# PCB_Arduino_V2_0_PC.net
KiCad netlist of a schematic drawn in EAGLE
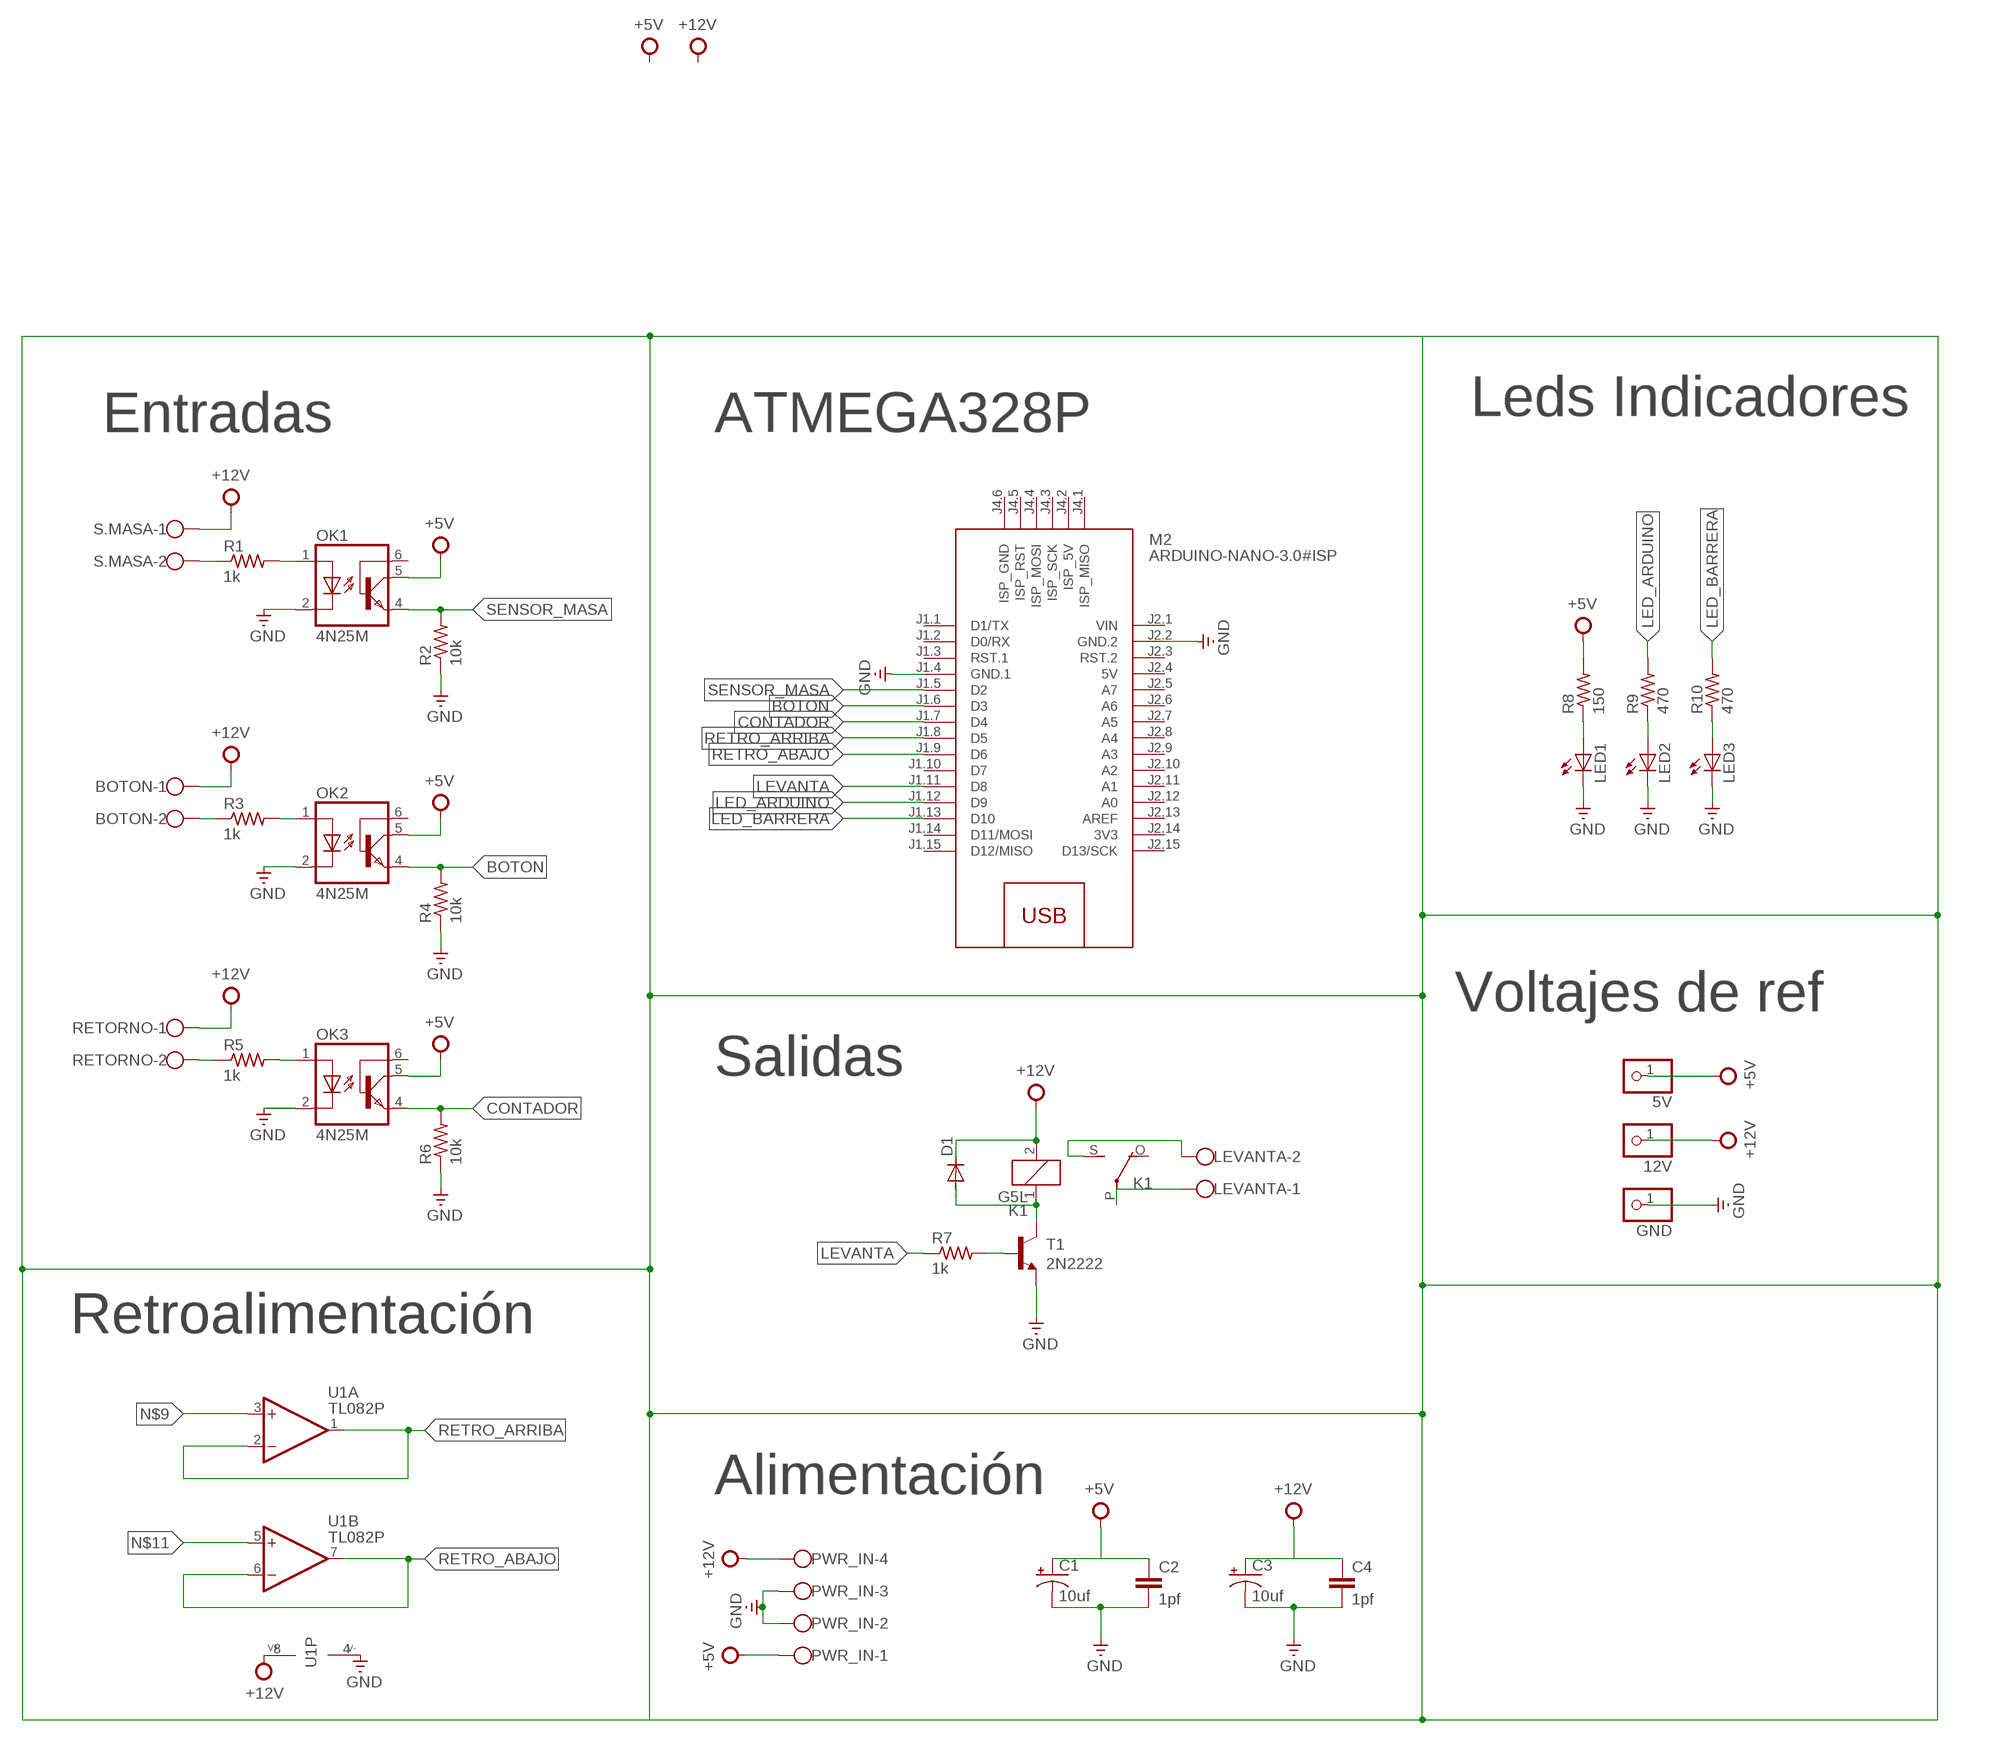
[diagram p0: schematic, sheet 1]

(export (version "E")
  (design (tool "Eeschema 10.0.6"))
  (components
    (comp (ref "5V")
      (value "PINHD-1X1")
      (footprint "eagle-import:1X01")
      (libsource (lib "eagle-import") (part "PINHD-1X1"))
    )
    (comp (ref "12V")
      (value "PINHD-1X1")
      (footprint "eagle-import:1X01")
      (libsource (lib "eagle-import") (part "PINHD-1X1"))
    )
    (comp (ref "BOTON")
      (value "W237-102")
      (footprint "eagle-import:W237-102")
      (fields (field (name "MPN") "237-102"))
      (libsource (lib "eagle-import") (part "W237-102"))
    )
    (comp (ref "C1")
      (value "10uf")
      (footprint "eagle-import:E2,5-6")
      (libsource (lib "eagle-import") (part "CPOL-USE2.5-6"))
    )
    (comp (ref "C2")
      (value "1pf")
      (footprint "eagle-import:C2.5-3")
      (libsource (lib "eagle-import") (part "C2,5-3"))
    )
    (comp (ref "C3")
      (value "10uf")
      (footprint "eagle-import:E2,5-6")
      (libsource (lib "eagle-import") (part "CPOL-USE2.5-6"))
    )
    (comp (ref "C4")
      (value "1pf")
      (footprint "eagle-import:C2.5-3")
      (libsource (lib "eagle-import") (part "C2,5-3"))
    )
    (comp (ref "D1")
      (value "1N4148DO35-7")
      (footprint "eagle-import:DO35-7")
      (libsource (lib "eagle-import") (part "1N4148DO35-7"))
    )
    (comp (ref "GND")
      (value "PINHD-1X1")
      (footprint "eagle-import:1X01")
      (libsource (lib "eagle-import") (part "PINHD-1X1"))
    )
    (comp (ref "K1")
      (value "G5L")
      (footprint "eagle-import:G5LE")
      (libsource (lib "eagle-import") (part "G5L"))
    )
    (comp (ref "LED1")
      (value "LED5MM")
      (footprint "eagle-import:LED5MM")
      (libsource (lib "eagle-import") (part "LED5MM"))
    )
    (comp (ref "LED2")
      (value "LED5MM")
      (footprint "eagle-import:LED5MM")
      (libsource (lib "eagle-import") (part "LED5MM"))
    )
    (comp (ref "LED3")
      (value "LED5MM")
      (footprint "eagle-import:LED5MM")
      (libsource (lib "eagle-import") (part "LED5MM"))
    )
    (comp (ref "LEVANTA")
      (value "W237-102")
      (footprint "eagle-import:W237-102")
      (fields (field (name "MPN") "237-102"))
      (libsource (lib "eagle-import") (part "W237-102"))
    )
    (comp (ref "M2")
      (value "ARDUINO-NANO-3.0#ISP")
      (footprint "eagle-import:ARDUINO-NANO-3.0#ISP")
      (libsource (lib "eagle-import") (part "ARDUINO-NANO-3.0#ISP"))
    )
    (comp (ref "OK1")
      (value "4N25M")
      (footprint "eagle-import:DIL06")
      (fields (field (name "MPN") "4N25-M"))
      (libsource (lib "eagle-import") (part "4N?M25"))
    )
    (comp (ref "OK2")
      (value "4N25M")
      (footprint "eagle-import:DIL06")
      (fields (field (name "MPN") "4N25-M"))
      (libsource (lib "eagle-import") (part "4N?M25"))
    )
    (comp (ref "OK3")
      (value "4N25M")
      (footprint "eagle-import:DIL06")
      (fields (field (name "MPN") "4N25-M"))
      (libsource (lib "eagle-import") (part "4N?M25"))
    )
    (comp (ref "PWR_IN")
      (value "W237-4")
      (footprint "eagle-import:W237-4")
      (libsource (lib "eagle-import") (part "W237-4"))
    )
    (comp (ref "R1")
      (value "1k")
      (footprint "eagle-import:0207_7")
      (libsource (lib "eagle-import") (part "R-US_0207/7"))
    )
    (comp (ref "R2")
      (value "10k")
      (footprint "eagle-import:0207_7")
      (libsource (lib "eagle-import") (part "R-US_0207/7"))
    )
    (comp (ref "R3")
      (value "1k")
      (footprint "eagle-import:0207_7")
      (libsource (lib "eagle-import") (part "R-US_0207/7"))
    )
    (comp (ref "R4")
      (value "10k")
      (footprint "eagle-import:0207_7")
      (libsource (lib "eagle-import") (part "R-US_0207/7"))
    )
    (comp (ref "R5")
      (value "1k")
      (footprint "eagle-import:0207_7")
      (libsource (lib "eagle-import") (part "R-US_0207/7"))
    )
    (comp (ref "R6")
      (value "10k")
      (footprint "eagle-import:0207_7")
      (libsource (lib "eagle-import") (part "R-US_0207/7"))
    )
    (comp (ref "R7")
      (value "1k")
      (footprint "eagle-import:0207_7")
      (libsource (lib "eagle-import") (part "R-US_0207/7"))
    )
    (comp (ref "R8")
      (value "150")
      (footprint "eagle-import:0207_7")
      (libsource (lib "eagle-import") (part "R-US_0207/7"))
    )
    (comp (ref "R9")
      (value "470")
      (footprint "eagle-import:0207_7")
      (libsource (lib "eagle-import") (part "R-US_0207/7"))
    )
    (comp (ref "R10")
      (value "470")
      (footprint "eagle-import:0207_7")
      (libsource (lib "eagle-import") (part "R-US_0207/7"))
    )
    (comp (ref "RETORNO")
      (value "W237-102")
      (footprint "eagle-import:W237-102")
      (fields (field (name "MPN") "237-102"))
      (libsource (lib "eagle-import") (part "W237-102"))
    )
    (comp (ref "S.MASA")
      (value "W237-102")
      (footprint "eagle-import:W237-102")
      (fields (field (name "MPN") "237-102"))
      (libsource (lib "eagle-import") (part "W237-102"))
    )
    (comp (ref "T1")
      (value "2N2222")
      (footprint "eagle-import:TO18")
      (libsource (lib "eagle-import") (part "2N2222"))
    )
    (comp (ref "U1")
      (value "TL082P")
      (footprint "eagle-import:DIL08")
      (libsource (lib "eagle-import") (part "TL082P"))
    )
  )
  (nets
    (net (code "1") (name "+5V") (class "Default")
      (node (ref "5V") (pin "1") (pinfunction "1_1") (pintype "passive"))
      (node (ref "C1") (pin "+") (pinfunction "+_+") (pintype "passive"))
      (node (ref "C2") (pin "1") (pinfunction "1_1") (pintype "passive"))
      (node (ref "OK1") (pin "5") (pinfunction "COL_5") (pintype "passive"))
      (node (ref "OK2") (pin "5") (pinfunction "COL_5") (pintype "passive"))
      (node (ref "OK3") (pin "5") (pinfunction "COL_5") (pintype "passive"))
      (node (ref "PWR_IN") (pin "1") (pinfunction "KL_1") (pintype "passive"))
      (node (ref "R8") (pin "2") (pinfunction "2_2") (pintype "passive"))
    )
    (net (code "2") (name "+12V") (class "Default")
      (node (ref "12V") (pin "1") (pinfunction "1_1") (pintype "passive"))
      (node (ref "BOTON") (pin "1") (pinfunction "KL_1") (pintype "passive"))
      (node (ref "C3") (pin "+") (pinfunction "+_+") (pintype "passive"))
      (node (ref "C4") (pin "1") (pinfunction "1_1") (pintype "passive"))
      (node (ref "D1") (pin "C") (pinfunction "C_C") (pintype "passive"))
      (node (ref "K1") (pin "2") (pinfunction "2_2") (pintype "passive"))
      (node (ref "PWR_IN") (pin "4") (pinfunction "KL_4") (pintype "passive"))
      (node (ref "RETORNO") (pin "1") (pinfunction "KL_1") (pintype "passive"))
      (node (ref "S.MASA") (pin "1") (pinfunction "KL_1") (pintype "passive"))
      (node (ref "U1") (pin "8") (pinfunction "V+_8") (pintype "power_in"))
    )
    (net (code "3") (name "/3V3") (class "Default")
      (node (ref "M2") (pin "J2.14") (pinfunction "3V3_J2.14") (pintype "power_in"))
    )
    (net (code "4") (name "/5V") (class "Default")
      (node (ref "M2") (pin "J2.4") (pinfunction "5V_J2.4") (pintype "power_in"))
    )
    (net (code "5") (name "/VIN") (class "Default")
      (node (ref "M2") (pin "J2.1") (pinfunction "VIN_J2.1") (pintype "power_in"))
    )
    (net (code "6") (name "BOTON") (class "Default")
      (node (ref "M2") (pin "J1.6") (pinfunction "D3_J1.6") (pintype "bidirectional"))
      (node (ref "OK2") (pin "4") (pinfunction "EMI_4") (pintype "passive"))
      (node (ref "R4") (pin "2") (pinfunction "2_2") (pintype "passive"))
    )
    (net (code "7") (name "CONTADOR") (class "Default")
      (node (ref "M2") (pin "J1.7") (pinfunction "D4_J1.7") (pintype "bidirectional"))
      (node (ref "OK3") (pin "4") (pinfunction "EMI_4") (pintype "passive"))
      (node (ref "R6") (pin "2") (pinfunction "2_2") (pintype "passive"))
    )
    (net (code "8") (name "GND") (class "Default")
      (node (ref "C1") (pin "-") (pinfunction "-_-") (pintype "passive"))
      (node (ref "C2") (pin "2") (pinfunction "2_2") (pintype "passive"))
      (node (ref "C3") (pin "-") (pinfunction "-_-") (pintype "passive"))
      (node (ref "C4") (pin "2") (pinfunction "2_2") (pintype "passive"))
      (node (ref "GND") (pin "1") (pinfunction "1_1") (pintype "passive"))
      (node (ref "LED1") (pin "K") (pinfunction "C_K") (pintype "passive"))
      (node (ref "LED2") (pin "K") (pinfunction "C_K") (pintype "passive"))
      (node (ref "LED3") (pin "K") (pinfunction "C_K") (pintype "passive"))
      (node (ref "M2") (pin "J1.4") (pinfunction "GND.1_J1.4") (pintype "power_in"))
      (node (ref "M2") (pin "J2.2") (pinfunction "GND.2_J2.2") (pintype "power_in"))
      (node (ref "OK1") (pin "2") (pinfunction "C_2") (pintype "passive"))
      (node (ref "OK2") (pin "2") (pinfunction "C_2") (pintype "passive"))
      (node (ref "OK3") (pin "2") (pinfunction "C_2") (pintype "passive"))
      (node (ref "PWR_IN") (pin "2") (pinfunction "KL_2") (pintype "passive"))
      (node (ref "PWR_IN") (pin "3") (pinfunction "KL_3") (pintype "passive"))
      (node (ref "R2") (pin "1") (pinfunction "1_1") (pintype "passive"))
      (node (ref "R4") (pin "1") (pinfunction "1_1") (pintype "passive"))
      (node (ref "R6") (pin "1") (pinfunction "1_1") (pintype "passive"))
      (node (ref "T1") (pin "1") (pinfunction "E_1") (pintype "passive"))
      (node (ref "U1") (pin "4") (pinfunction "V-_4") (pintype "power_in"))
    )
    (net (code "9") (name "LED_ARDUINO") (class "Default")
      (node (ref "M2") (pin "J1.12") (pinfunction "D9_J1.12") (pintype "bidirectional"))
      (node (ref "R9") (pin "2") (pinfunction "2_2") (pintype "passive"))
    )
    (net (code "10") (name "LED_BARRERA") (class "Default")
      (node (ref "M2") (pin "J1.13") (pinfunction "D10_J1.13") (pintype "bidirectional"))
      (node (ref "R10") (pin "2") (pinfunction "2_2") (pintype "passive"))
    )
    (net (code "11") (name "LEVANTA") (class "Default")
      (node (ref "M2") (pin "J1.11") (pinfunction "D8_J1.11") (pintype "bidirectional"))
      (node (ref "R7") (pin "1") (pinfunction "1_1") (pintype "passive"))
    )
    (net (code "12") (name "N$9") (class "Default")
      (node (ref "U1") (pin "3") (pinfunction "+IN_3") (pintype "input"))
    )
    (net (code "13") (name "N$11") (class "Default")
      (node (ref "U1") (pin "5") (pinfunction "+IN_5") (pintype "input"))
    )
    (net (code "14") (name "Net-(BOTONB-KL)") (class "Default")
      (node (ref "BOTON") (pin "2") (pinfunction "KL_2") (pintype "passive"))
      (node (ref "R3") (pin "1") (pinfunction "1_1") (pintype "passive"))
    )
    (net (code "15") (name "Net-(LED1-PadA)") (class "Default")
      (node (ref "LED1") (pin "A") (pinfunction "A_A") (pintype "passive"))
      (node (ref "R8") (pin "1") (pinfunction "1_1") (pintype "passive"))
    )
    (net (code "16") (name "Net-(LED2-PadA)") (class "Default")
      (node (ref "LED2") (pin "A") (pinfunction "A_A") (pintype "passive"))
      (node (ref "R9") (pin "1") (pinfunction "1_1") (pintype "passive"))
    )
    (net (code "17") (name "Net-(LED3-PadA)") (class "Default")
      (node (ref "LED3") (pin "A") (pinfunction "A_A") (pintype "passive"))
      (node (ref "R10") (pin "1") (pinfunction "1_1") (pintype "passive"))
    )
    (net (code "18") (name "Net-(LEVANTAA-KL)") (class "Default")
      (node (ref "K1") (pin "P") (pinfunction "P_P") (pintype "passive"))
      (node (ref "LEVANTA") (pin "1") (pinfunction "KL_1") (pintype "passive"))
    )
    (net (code "19") (name "Net-(LEVANTAB-KL)") (class "Default")
      (node (ref "K1") (pin "S") (pinfunction "S_S") (pintype "passive"))
      (node (ref "LEVANTA") (pin "2") (pinfunction "KL_2") (pintype "passive"))
    )
    (net (code "20") (name "Net-(OK1-A)") (class "Default")
      (node (ref "OK1") (pin "1") (pinfunction "A_1") (pintype "passive"))
      (node (ref "R1") (pin "2") (pinfunction "2_2") (pintype "passive"))
    )
    (net (code "21") (name "Net-(OK2-A)") (class "Default")
      (node (ref "OK2") (pin "1") (pinfunction "A_1") (pintype "passive"))
      (node (ref "R3") (pin "2") (pinfunction "2_2") (pintype "passive"))
    )
    (net (code "22") (name "Net-(OK3-A)") (class "Default")
      (node (ref "OK3") (pin "1") (pinfunction "A_1") (pintype "passive"))
      (node (ref "R5") (pin "2") (pinfunction "2_2") (pintype "passive"))
    )
    (net (code "23") (name "Net-(RETORNOB-KL)") (class "Default")
      (node (ref "R5") (pin "1") (pinfunction "1_1") (pintype "passive"))
      (node (ref "RETORNO") (pin "2") (pinfunction "KL_2") (pintype "passive"))
    )
    (net (code "24") (name "Net-(S.MASAB-KL)") (class "Default")
      (node (ref "R1") (pin "1") (pinfunction "1_1") (pintype "passive"))
      (node (ref "S.MASA") (pin "2") (pinfunction "KL_2") (pintype "passive"))
    )
    (net (code "25") (name "Net-(T1-B)") (class "Default")
      (node (ref "R7") (pin "2") (pinfunction "2_2") (pintype "passive"))
      (node (ref "T1") (pin "2") (pinfunction "B_2") (pintype "passive"))
    )
    (net (code "26") (name "Net-(T1-C)") (class "Default")
      (node (ref "D1") (pin "A") (pinfunction "A_A") (pintype "passive"))
      (node (ref "K1") (pin "1") (pinfunction "1_1") (pintype "passive"))
      (node (ref "T1") (pin "3") (pinfunction "C_3") (pintype "passive"))
    )
    (net (code "27") (name "RETRO_ABAJO") (class "Default")
      (node (ref "M2") (pin "J1.9") (pinfunction "D6_J1.9") (pintype "bidirectional"))
      (node (ref "U1") (pin "6") (pinfunction "-IN_6") (pintype "input"))
      (node (ref "U1") (pin "7") (pinfunction "OUT_7") (pintype "output"))
    )
    (net (code "28") (name "RETRO_ARRIBA") (class "Default")
      (node (ref "M2") (pin "J1.8") (pinfunction "D5_J1.8") (pintype "bidirectional"))
      (node (ref "U1") (pin "1") (pinfunction "OUT_1") (pintype "output"))
      (node (ref "U1") (pin "2") (pinfunction "-IN_2") (pintype "input"))
    )
    (net (code "29") (name "SENSOR_MASA") (class "Default")
      (node (ref "M2") (pin "J1.5") (pinfunction "D2_J1.5") (pintype "bidirectional"))
      (node (ref "OK1") (pin "4") (pinfunction "EMI_4") (pintype "passive"))
      (node (ref "R2") (pin "2") (pinfunction "2_2") (pintype "passive"))
    )
    (net (code "30") (name "unconnected-(K1-PadO)") (class "Default")
      (node (ref "K1") (pin "O") (pinfunction "O_O") (pintype "passive"))
    )
    (net (code "31") (name "unconnected-(M2-A0-PadJ2.12)") (class "Default")
      (node (ref "M2") (pin "J2.12") (pinfunction "A0_J2.12") (pintype "bidirectional"))
    )
    (net (code "32") (name "unconnected-(M2-A1-PadJ2.11)") (class "Default")
      (node (ref "M2") (pin "J2.11") (pinfunction "A1_J2.11") (pintype "bidirectional"))
    )
    (net (code "33") (name "unconnected-(M2-A2-PadJ2.10)") (class "Default")
      (node (ref "M2") (pin "J2.10") (pinfunction "A2_J2.10") (pintype "bidirectional"))
    )
    (net (code "34") (name "unconnected-(M2-A3-PadJ2.9)") (class "Default")
      (node (ref "M2") (pin "J2.9") (pinfunction "A3_J2.9") (pintype "bidirectional"))
    )
    (net (code "35") (name "unconnected-(M2-A4-PadJ2.8)") (class "Default")
      (node (ref "M2") (pin "J2.8") (pinfunction "A4_J2.8") (pintype "bidirectional"))
    )
    (net (code "36") (name "unconnected-(M2-A5-PadJ2.7)") (class "Default")
      (node (ref "M2") (pin "J2.7") (pinfunction "A5_J2.7") (pintype "bidirectional"))
    )
    (net (code "37") (name "unconnected-(M2-A6-PadJ2.6)") (class "Default")
      (node (ref "M2") (pin "J2.6") (pinfunction "A6_J2.6") (pintype "bidirectional"))
    )
    (net (code "38") (name "unconnected-(M2-A7-PadJ2.5)") (class "Default")
      (node (ref "M2") (pin "J2.5") (pinfunction "A7_J2.5") (pintype "bidirectional"))
    )
    (net (code "39") (name "unconnected-(M2-AREF-PadJ2.13)") (class "Default")
      (node (ref "M2") (pin "J2.13") (pinfunction "AREF_J2.13") (pintype "bidirectional"))
    )
    (net (code "40") (name "unconnected-(M2-D0{slash}RX-PadJ1.2)") (class "Default")
      (node (ref "M2") (pin "J1.2") (pinfunction "D0/RX_J1.2") (pintype "bidirectional"))
    )
    (net (code "41") (name "unconnected-(M2-D1{slash}TX-PadJ1.1)") (class "Default")
      (node (ref "M2") (pin "J1.1") (pinfunction "D1/TX_J1.1") (pintype "bidirectional"))
    )
    (net (code "42") (name "unconnected-(M2-D7-PadJ1.10)") (class "Default")
      (node (ref "M2") (pin "J1.10") (pinfunction "D7_J1.10") (pintype "bidirectional"))
    )
    (net (code "43") (name "unconnected-(M2-D11{slash}MOSI-PadJ1.14)") (class "Default")
      (node (ref "M2") (pin "J1.14") (pinfunction "D11/MOSI_J1.14") (pintype "bidirectional"))
    )
    (net (code "44") (name "unconnected-(M2-D12{slash}MISO-PadJ1.15)") (class "Default")
      (node (ref "M2") (pin "J1.15") (pinfunction "D12/MISO_J1.15") (pintype "bidirectional"))
    )
    (net (code "45") (name "unconnected-(M2-D13{slash}SCK-PadJ2.15)") (class "Default")
      (node (ref "M2") (pin "J2.15") (pinfunction "D13/SCK_J2.15") (pintype "bidirectional"))
    )
    (net (code "46") (name "unconnected-(M2-ISP_5V-PadJ4.2)") (class "Default")
      (node (ref "M2") (pin "J4.2") (pinfunction "ISP_5V_J4.2") (pintype "bidirectional"))
    )
    (net (code "47") (name "unconnected-(M2-ISP_GND-PadJ4.6)") (class "Default")
      (node (ref "M2") (pin "J4.6") (pinfunction "ISP_GND_J4.6") (pintype "bidirectional"))
    )
    (net (code "48") (name "unconnected-(M2-ISP_MISO-PadJ4.1)") (class "Default")
      (node (ref "M2") (pin "J4.1") (pinfunction "ISP_MISO_J4.1") (pintype "bidirectional"))
    )
    (net (code "49") (name "unconnected-(M2-ISP_MOSI-PadJ4.4)") (class "Default")
      (node (ref "M2") (pin "J4.4") (pinfunction "ISP_MOSI_J4.4") (pintype "bidirectional"))
    )
    (net (code "50") (name "unconnected-(M2-ISP_RST-PadJ4.5)") (class "Default")
      (node (ref "M2") (pin "J4.5") (pinfunction "ISP_RST_J4.5") (pintype "bidirectional"))
    )
    (net (code "51") (name "unconnected-(M2-ISP_SCK-PadJ4.3)") (class "Default")
      (node (ref "M2") (pin "J4.3") (pinfunction "ISP_SCK_J4.3") (pintype "bidirectional"))
    )
    (net (code "52") (name "unconnected-(M2-RST.1-PadJ1.3)") (class "Default")
      (node (ref "M2") (pin "J1.3") (pinfunction "RST.1_J1.3") (pintype "bidirectional"))
    )
    (net (code "53") (name "unconnected-(M2-RST.2-PadJ2.3)") (class "Default")
      (node (ref "M2") (pin "J2.3") (pinfunction "RST.2_J2.3") (pintype "bidirectional"))
    )
    (net (code "54") (name "unconnected-(OK1-BAS-Pad6)") (class "Default")
      (node (ref "OK1") (pin "6") (pinfunction "BAS_6") (pintype "passive"))
    )
    (net (code "55") (name "unconnected-(OK2-BAS-Pad6)") (class "Default")
      (node (ref "OK2") (pin "6") (pinfunction "BAS_6") (pintype "passive"))
    )
    (net (code "56") (name "unconnected-(OK3-BAS-Pad6)") (class "Default")
      (node (ref "OK3") (pin "6") (pinfunction "BAS_6") (pintype "passive"))
    )
  )
)
